# AFE.net
KiCad netlist of a schematic drawn in Altium Designer
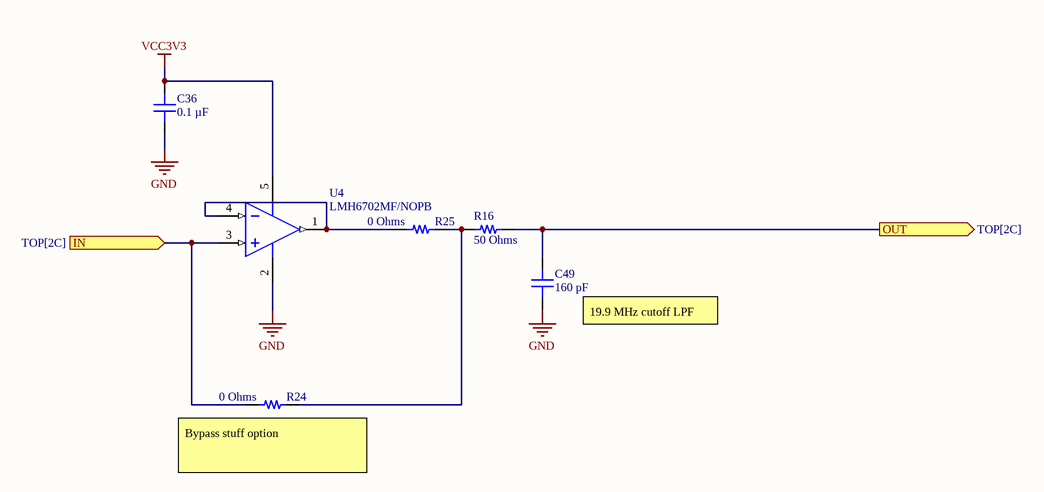
[diagram p0: AFE.SchDoc]

(export (version "E")
  (design (tool "Eeschema 10.0.6"))
  (components
    (comp (ref "C36")
      (value "0.1 µF")
      (footprint "CAP 0402_1005")
      (description "CAP CER 0.1UF 50V X5R 0402")
      (fields
        (field (name "PART NUMBER") "CGA2B3X5R1H104M050BB")
        (field (name "MANUFACTURER") "TDK Corporation")
      )
      (libsource (lib "Celestial") (part "Capacitor"))
    )
    (comp (ref "C49")
      (value "160 pF")
      (footprint "CAP 0603_1608")
      (description "CAP CER 160PF 50V C0G/NPO 0603")
      (fields (field (name "PART NUMBER") "CC0603JRNPO9BN161") (field (name "MANUFACTURER") "Yageo"))
      (libsource (lib "Celestial") (part "Capacitor"))
    )
    (comp (ref "R16")
      (value "50 Ohms")
      (footprint "RES 0603_1608")
      (description "RES 50 OHM 5% 1/8W 0603")
      (fields (field (name "PART NUMBER") "CH0603-50RJNTA") (field (name "MANUFACTURER") "Vishay Sfernice"))
      (libsource (lib "Celestial") (part "Resistor"))
    )
    (comp (ref "R24")
      (value "0 Ohms")
      (footprint "RES 0603_1608")
      (description "RES SMD 0 OHM JUMPER 1/2W 0603")
      (fields (field (name "PART NUMBER") "5110") (field (name "MANUFACTURER") "Keystone Electronics"))
      (libsource (lib "Celestial") (part "Resistor"))
    )
    (comp (ref "R25")
      (value "0 Ohms")
      (footprint "RES 0603_1608")
      (description "RES SMD 0 OHM JUMPER 1/2W 0603")
      (fields (field (name "PART NUMBER") "5110") (field (name "MANUFACTURER") "Keystone Electronics"))
      (libsource (lib "Celestial") (part "Resistor"))
    )
    (comp (ref "U4")
      (value "LMH6702MF/NOPB")
      (footprint "DBV0005A_N")
      (description "1.7 GHz, Ultra Low Distortion, Wideband Op Amp, 5-pin SOT-23, Pb-Free")
      (fields (field (name "MANUFACTURER") "Texas Instruments"))
      (libsource (lib "Altium Content Vault") (part "AMP-OPA-LM7121-5"))
    )
  )
  (nets
    (net (code "1") (name "/IN") (class "Default")
      (node (ref "R24") (pin "1") (pinfunction "1_1") (pintype "passive"))
      (node (ref "U4") (pin "3") (pinfunction "IN+_3") (pintype "input"))
    )
    (net (code "2") (name "/OUT") (class "Default")
      (node (ref "C49") (pin "2") (pinfunction "2_2") (pintype "passive"))
      (node (ref "R16") (pin "2") (pinfunction "2_2") (pintype "passive"))
    )
    (net (code "3") (name "GND") (class "Default")
      (node (ref "C36") (pin "1") (pinfunction "1_1") (pintype "passive"))
      (node (ref "C49") (pin "1") (pinfunction "1_1") (pintype "passive"))
      (node (ref "U4") (pin "2") (pinfunction "V-_2") (pintype "power_in"))
    )
    (net (code "4") (name "Net-(R16-Pad1)") (class "Default")
      (node (ref "R16") (pin "1") (pinfunction "1_1") (pintype "passive"))
      (node (ref "R24") (pin "2") (pinfunction "2_2") (pintype "passive"))
      (node (ref "R25") (pin "2") (pinfunction "2_2") (pintype "passive"))
    )
    (net (code "5") (name "Net-(U4-IN-)") (class "Default")
      (node (ref "R25") (pin "1") (pinfunction "1_1") (pintype "passive"))
      (node (ref "U4") (pin "1") (pinfunction "OUT_1") (pintype "output"))
      (node (ref "U4") (pin "4") (pinfunction "IN-_4") (pintype "input"))
    )
    (net (code "6") (name "VCC3V3") (class "Default")
      (node (ref "C36") (pin "2") (pinfunction "2_2") (pintype "passive"))
      (node (ref "U4") (pin "5") (pinfunction "V+_5") (pintype "power_in"))
    )
  )
)
